# nano_power.net
KiCad netlist of a schematic drawn in EAGLE
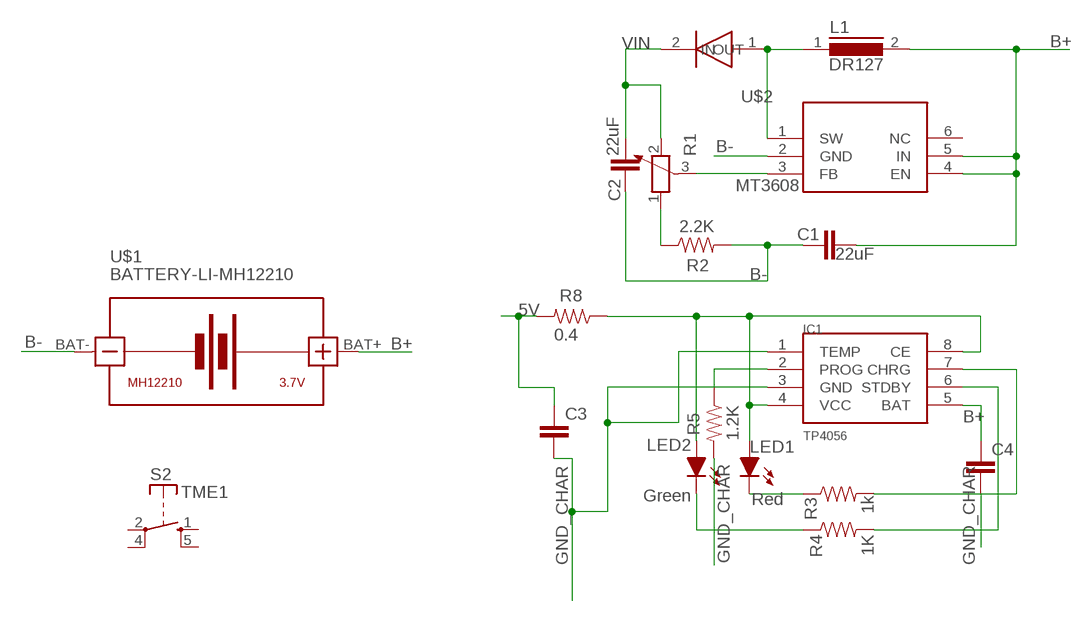
[diagram p0: schematic, sheet 1]

(export (version "E")
  (design (tool "Eeschema 10.0.6"))
  (components
    (comp (ref "C1")
      (value "22uF")
      (footprint "eagle-import:SMD0805")
      (libsource (lib "eagle-import") (part "CAP_0805"))
    )
    (comp (ref "C2")
      (value "22uF")
      (footprint "eagle-import:SMD0805")
      (libsource (lib "eagle-import") (part "CAP_0805"))
    )
    (comp (ref "C3")
      (value "CAP_0805")
      (footprint "eagle-import:SMD0805")
      (libsource (lib "eagle-import") (part "CAP_0805"))
    )
    (comp (ref "C4")
      (value "CAP_0805")
      (footprint "eagle-import:SMD0805")
      (libsource (lib "eagle-import") (part "CAP_0805"))
    )
    (comp (ref "IC1")
      (value "TP4056")
      (footprint "eagle-import:SOP-8")
      (libsource (lib "eagle-import") (part "TP4056"))
    )
    (comp (ref "L1")
      (value "DR127")
      (footprint "eagle-import:DR127")
      (libsource (lib "eagle-import") (part "DR127"))
    )
    (comp (ref "LED1")
      (value "Red")
      (footprint "eagle-import:LED_0603")
      (libsource (lib "eagle-import") (part "LED_0603"))
    )
    (comp (ref "LED2")
      (value "Green")
      (footprint "eagle-import:LED_0603")
      (libsource (lib "eagle-import") (part "LED_0603"))
    )
    (comp (ref "R1")
      (value "POTENTIOMETER_PT-10")
      (footprint "eagle-import:PT-10")
      (libsource (lib "eagle-import") (part "POTENTIOMETER_PT-10"))
    )
    (comp (ref "R2")
      (value "2.2K")
      (footprint "eagle-import:SMD0603")
      (libsource (lib "eagle-import") (part "RES_0603"))
    )
    (comp (ref "R3")
      (value "1k")
      (footprint "eagle-import:SMD0603")
      (libsource (lib "eagle-import") (part "RES_0603"))
    )
    (comp (ref "R4")
      (value "1K")
      (footprint "eagle-import:SMD0603")
      (libsource (lib "eagle-import") (part "RES_0603"))
    )
    (comp (ref "R5")
      (value "1.2K")
      (footprint "eagle-import:SMD0603")
      (libsource (lib "eagle-import") (part "RES_0603"))
    )
    (comp (ref "R8")
      (value "0.4")
      (footprint "eagle-import:SMD0805")
      (libsource (lib "eagle-import") (part "RES_0805"))
    )
    (comp (ref "S2")
      (value "TME1")
      (footprint "eagle-import:TME1")
      (libsource (lib "eagle-import") (part "TME1"))
    )
    (comp (ref "U$1")
      (value "BATTERY-LI-MH12210")
      (footprint "eagle-import:BATTERY-LI-MH12210")
      (libsource (lib "eagle-import") (part "BATTERY-LI-MH12210"))
    )
    (comp (ref "U$2")
      (value "MT3608")
      (footprint "eagle-import:SOT23-6")
      (libsource (lib "eagle-import") (part "MT3608"))
    )
    (comp (ref "U$3")
      (value "SMA-SS34")
      (footprint "eagle-import:SMA-SS34")
      (libsource (lib "eagle-import") (part "SMA-SS34"))
    )
  )
  (nets
    (net (code "1") (name "/5V") (class "Default")
      (node (ref "C3") (pin "1") (pinfunction "1_1") (pintype "passive"))
      (node (ref "R8") (pin "2") (pinfunction "2_2") (pintype "passive"))
    )
    (net (code "2") (name "/B+") (class "Default")
      (node (ref "C1") (pin "2") (pinfunction "2_2") (pintype "passive"))
      (node (ref "C4") (pin "1") (pinfunction "1_1") (pintype "passive"))
      (node (ref "IC1") (pin "5") (pinfunction "BAT_5") (pintype "bidirectional"))
      (node (ref "L1") (pin "2") (pinfunction "2_2") (pintype "passive"))
      (node (ref "U$1") (pin "BAT+") (pinfunction "BAT+_BAT+") (pintype "power_in"))
      (node (ref "U$2") (pin "4") (pinfunction "EN_4") (pintype "input"))
      (node (ref "U$2") (pin "5") (pinfunction "IN_5") (pintype "power_in"))
    )
    (net (code "3") (name "/B-") (class "Default")
      (node (ref "C1") (pin "1") (pinfunction "1_1") (pintype "passive"))
      (node (ref "C2") (pin "1") (pinfunction "1_1") (pintype "passive"))
      (node (ref "R2") (pin "2") (pinfunction "2_2") (pintype "passive"))
      (node (ref "U$1") (pin "BAT-") (pinfunction "BAT-_BAT-") (pintype "power_in"))
      (node (ref "U$2") (pin "2") (pinfunction "GND_2") (pintype "power_in"))
    )
    (net (code "4") (name "/GND_CHAR") (class "Default")
      (node (ref "C3") (pin "2") (pinfunction "2_2") (pintype "passive"))
      (node (ref "C4") (pin "2") (pinfunction "2_2") (pintype "passive"))
      (node (ref "IC1") (pin "1") (pinfunction "TEMP_1") (pintype "bidirectional"))
      (node (ref "IC1") (pin "3") (pinfunction "GND_3") (pintype "bidirectional"))
      (node (ref "R5") (pin "2") (pinfunction "2_2") (pintype "passive"))
    )
    (net (code "5") (name "/VIN") (class "Default")
      (node (ref "C2") (pin "2") (pinfunction "2_2") (pintype "passive"))
      (node (ref "R1") (pin "2") (pinfunction "2_2") (pintype "passive"))
      (node (ref "U$3") (pin "2") (pinfunction "OUT_2") (pintype "bidirectional"))
    )
    (net (code "6") (name "Net-(IC1-CE)") (class "Default")
      (node (ref "IC1") (pin "4") (pinfunction "VCC_4") (pintype "bidirectional"))
      (node (ref "IC1") (pin "8") (pinfunction "CE_8") (pintype "bidirectional"))
      (node (ref "LED1") (pin "A") (pinfunction "A_A") (pintype "passive"))
      (node (ref "LED2") (pin "A") (pinfunction "A_A") (pintype "passive"))
      (node (ref "R8") (pin "1") (pinfunction "1_1") (pintype "passive"))
    )
    (net (code "7") (name "Net-(IC1-CHRG)") (class "Default")
      (node (ref "IC1") (pin "7") (pinfunction "CHRG_7") (pintype "bidirectional"))
      (node (ref "R3") (pin "2") (pinfunction "2_2") (pintype "passive"))
    )
    (net (code "8") (name "Net-(IC1-PROG)") (class "Default")
      (node (ref "IC1") (pin "2") (pinfunction "PROG_2") (pintype "bidirectional"))
      (node (ref "R5") (pin "1") (pinfunction "1_1") (pintype "passive"))
    )
    (net (code "9") (name "Net-(IC1-STDBY)") (class "Default")
      (node (ref "IC1") (pin "6") (pinfunction "STDBY_6") (pintype "bidirectional"))
      (node (ref "R4") (pin "2") (pinfunction "2_2") (pintype "passive"))
    )
    (net (code "10") (name "Net-(LED1-PadC)") (class "Default")
      (node (ref "LED1") (pin "C") (pinfunction "C_C") (pintype "passive"))
      (node (ref "R3") (pin "1") (pinfunction "1_1") (pintype "passive"))
    )
    (net (code "11") (name "Net-(LED2-PadC)") (class "Default")
      (node (ref "LED2") (pin "C") (pinfunction "C_C") (pintype "passive"))
      (node (ref "R4") (pin "1") (pinfunction "1_1") (pintype "passive"))
    )
    (net (code "12") (name "Net-(R1-Pad1)") (class "Default")
      (node (ref "R1") (pin "1") (pinfunction "1_1") (pintype "passive"))
      (node (ref "R2") (pin "1") (pinfunction "1_1") (pintype "passive"))
    )
    (net (code "13") (name "Net-(U$2-FB)") (class "Default")
      (node (ref "R1") (pin "3") (pinfunction "3_3") (pintype "passive"))
      (node (ref "U$2") (pin "3") (pinfunction "FB_3") (pintype "input"))
    )
    (net (code "14") (name "Net-(U$2-SW)") (class "Default")
      (node (ref "L1") (pin "1") (pinfunction "1_1") (pintype "passive"))
      (node (ref "U$2") (pin "1") (pinfunction "SW_1") (pintype "output"))
      (node (ref "U$3") (pin "1") (pinfunction "IN_1") (pintype "input"))
    )
    (net (code "15") (name "unconnected-(S2-P-Pad2)") (class "Default")
      (node (ref "S2") (pin "2") (pinfunction "P_2") (pintype "passive"))
    )
    (net (code "16") (name "unconnected-(S2-P-Pad4)") (class "Default")
      (node (ref "S2") (pin "4") (pinfunction "P_4") (pintype "passive"))
    )
    (net (code "17") (name "unconnected-(S2-S-Pad1)") (class "Default")
      (node (ref "S2") (pin "1") (pinfunction "S_1") (pintype "passive"))
    )
    (net (code "18") (name "unconnected-(S2-S-Pad5)") (class "Default")
      (node (ref "S2") (pin "5") (pinfunction "S_5") (pintype "passive"))
    )
    (net (code "19") (name "unconnected-(U$2-NC-Pad6)") (class "Default")
      (node (ref "U$2") (pin "6") (pinfunction "NC_6") (pintype "no_connect"))
    )
  )
)
